# 7474-strobe-generator.net
KiCad netlist of a schematic drawn in EAGLE
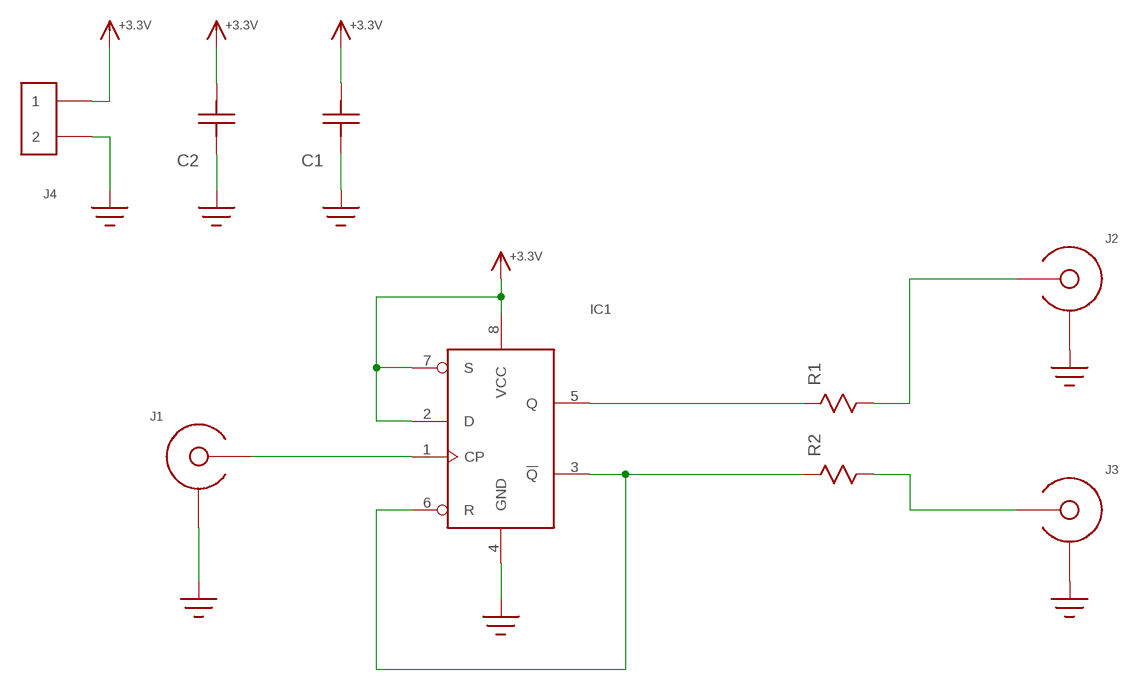
[diagram p0: schematic, sheet 1]

(export (version "E")
  (design (tool "Eeschema 10.0.6"))
  (components
    (comp (ref "C1")
      (value "C0603")
      (footprint "eagle-import:C0603")
      (libsource (lib "eagle-import") (part "C0603"))
    )
    (comp (ref "C2")
      (value "C1206")
      (footprint "eagle-import:1206")
      (libsource (lib "eagle-import") (part "C1206"))
    )
    (comp (ref "IC1")
      (value "74LVC2G74")
      (footprint "eagle-import:SSOP8")
      (libsource (lib "eagle-import") (part "74LVC2G74"))
    )
    (comp (ref "J1")
      (value "SMA-EDGE-LAUNCH4020_TAPER")
      (footprint "eagle-import:SMA_EDGE_LAUNCH_2L_4020_TAPER")
      (libsource (lib "eagle-import") (part "SMA-EDGE-LAUNCH4020_TAPER"))
    )
    (comp (ref "J2")
      (value "SMA-EDGE-LAUNCH4020_TAPER")
      (footprint "eagle-import:SMA_EDGE_LAUNCH_2L_4020_TAPER")
      (libsource (lib "eagle-import") (part "SMA-EDGE-LAUNCH4020_TAPER"))
    )
    (comp (ref "J3")
      (value "SMA-EDGE-LAUNCH4020_TAPER")
      (footprint "eagle-import:SMA_EDGE_LAUNCH_2L_4020_TAPER")
      (libsource (lib "eagle-import") (part "SMA-EDGE-LAUNCH4020_TAPER"))
    )
    (comp (ref "J4")
      (value "HEADER_2PIN")
      (footprint "eagle-import:HEADER_2PIN")
      (libsource (lib "eagle-import") (part "HEADER_2PIN"))
    )
    (comp (ref "R1")
      (value "R0603")
      (footprint "eagle-import:R0603")
      (libsource (lib "eagle-import") (part "R0603"))
    )
    (comp (ref "R2")
      (value "R0603")
      (footprint "eagle-import:R0603")
      (libsource (lib "eagle-import") (part "R0603"))
    )
  )
  (nets
    (net (code "1") (name "+3.3V") (class "Default")
      (node (ref "C1") (pin "P$1") (pinfunction "P$1_P$1") (pintype "bidirectional"))
      (node (ref "C2") (pin "P$1") (pinfunction "P$1_P$1") (pintype "bidirectional"))
      (node (ref "IC1") (pin "2") (pinfunction "D_2") (pintype "bidirectional"))
      (node (ref "IC1") (pin "7") (pinfunction "S_7") (pintype "bidirectional"))
      (node (ref "IC1") (pin "8") (pinfunction "VCC_8") (pintype "bidirectional"))
      (node (ref "J4") (pin "1") (pinfunction "1_1") (pintype "bidirectional"))
    )
    (net (code "2") (name "GND") (class "Default")
      (node (ref "C1") (pin "P$2") (pinfunction "P$2_P$2") (pintype "bidirectional"))
      (node (ref "C2") (pin "P$2") (pinfunction "P$2_P$2") (pintype "bidirectional"))
      (node (ref "IC1") (pin "4") (pinfunction "GND_4") (pintype "bidirectional"))
      (node (ref "J1") (pin "BOTTOM_GND") (pinfunction "SHIELD_BOTTOM_GND") (pintype "bidirectional"))
      (node (ref "J1") (pin "GND@1") (pinfunction "SHIELD_GND@1") (pintype "bidirectional"))
      (node (ref "J1") (pin "GND@14") (pinfunction "SHIELD_GND@14") (pintype "bidirectional"))
      (node (ref "J1") (pin "GND@15") (pinfunction "SHIELD_GND@15") (pintype "bidirectional"))
      (node (ref "J1") (pin "GND@16") (pinfunction "SHIELD_GND@16") (pintype "bidirectional"))
      (node (ref "J1") (pin "GND@17") (pinfunction "SHIELD_GND@17") (pintype "bidirectional"))
      (node (ref "J1") (pin "GND@2") (pinfunction "SHIELD_GND@2") (pintype "bidirectional"))
      (node (ref "J1") (pin "GND@3") (pinfunction "SHIELD_GND@3") (pintype "bidirectional"))
      (node (ref "J1") (pin "GND@4") (pinfunction "SHIELD_GND@4") (pintype "bidirectional"))
      (node (ref "J1") (pin "GND@5") (pinfunction "SHIELD_GND@5") (pintype "bidirectional"))
      (node (ref "J1") (pin "GND@6") (pinfunction "SHIELD_GND@6") (pintype "bidirectional"))
      (node (ref "J1") (pin "GND@7") (pinfunction "SHIELD_GND@7") (pintype "bidirectional"))
      (node (ref "J1") (pin "GND@8") (pinfunction "SHIELD_GND@8") (pintype "bidirectional"))
      (node (ref "J1") (pin "GND_PAD1") (pinfunction "SHIELD_GND_PAD1") (pintype "bidirectional"))
      (node (ref "J1") (pin "GND_PAD2") (pinfunction "SHIELD_GND_PAD2") (pintype "bidirectional"))
      (node (ref "J1") (pin "P$1") (pinfunction "SHIELD_P$1") (pintype "bidirectional"))
      (node (ref "J1") (pin "P$2") (pinfunction "SHIELD_P$2") (pintype "bidirectional"))
      (node (ref "J2") (pin "BOTTOM_GND") (pinfunction "SHIELD_BOTTOM_GND") (pintype "bidirectional"))
      (node (ref "J2") (pin "GND@1") (pinfunction "SHIELD_GND@1") (pintype "bidirectional"))
      (node (ref "J2") (pin "GND@14") (pinfunction "SHIELD_GND@14") (pintype "bidirectional"))
      (node (ref "J2") (pin "GND@15") (pinfunction "SHIELD_GND@15") (pintype "bidirectional"))
      (node (ref "J2") (pin "GND@16") (pinfunction "SHIELD_GND@16") (pintype "bidirectional"))
      (node (ref "J2") (pin "GND@17") (pinfunction "SHIELD_GND@17") (pintype "bidirectional"))
      (node (ref "J2") (pin "GND@2") (pinfunction "SHIELD_GND@2") (pintype "bidirectional"))
      (node (ref "J2") (pin "GND@3") (pinfunction "SHIELD_GND@3") (pintype "bidirectional"))
      (node (ref "J2") (pin "GND@4") (pinfunction "SHIELD_GND@4") (pintype "bidirectional"))
      (node (ref "J2") (pin "GND@5") (pinfunction "SHIELD_GND@5") (pintype "bidirectional"))
      (node (ref "J2") (pin "GND@6") (pinfunction "SHIELD_GND@6") (pintype "bidirectional"))
      (node (ref "J2") (pin "GND@7") (pinfunction "SHIELD_GND@7") (pintype "bidirectional"))
      (node (ref "J2") (pin "GND@8") (pinfunction "SHIELD_GND@8") (pintype "bidirectional"))
      (node (ref "J2") (pin "GND_PAD1") (pinfunction "SHIELD_GND_PAD1") (pintype "bidirectional"))
      (node (ref "J2") (pin "GND_PAD2") (pinfunction "SHIELD_GND_PAD2") (pintype "bidirectional"))
      (node (ref "J2") (pin "P$1") (pinfunction "SHIELD_P$1") (pintype "bidirectional"))
      (node (ref "J2") (pin "P$2") (pinfunction "SHIELD_P$2") (pintype "bidirectional"))
      (node (ref "J3") (pin "BOTTOM_GND") (pinfunction "SHIELD_BOTTOM_GND") (pintype "bidirectional"))
      (node (ref "J3") (pin "GND@1") (pinfunction "SHIELD_GND@1") (pintype "bidirectional"))
      (node (ref "J3") (pin "GND@14") (pinfunction "SHIELD_GND@14") (pintype "bidirectional"))
      (node (ref "J3") (pin "GND@15") (pinfunction "SHIELD_GND@15") (pintype "bidirectional"))
      (node (ref "J3") (pin "GND@16") (pinfunction "SHIELD_GND@16") (pintype "bidirectional"))
      (node (ref "J3") (pin "GND@17") (pinfunction "SHIELD_GND@17") (pintype "bidirectional"))
      (node (ref "J3") (pin "GND@2") (pinfunction "SHIELD_GND@2") (pintype "bidirectional"))
      (node (ref "J3") (pin "GND@3") (pinfunction "SHIELD_GND@3") (pintype "bidirectional"))
      (node (ref "J3") (pin "GND@4") (pinfunction "SHIELD_GND@4") (pintype "bidirectional"))
      (node (ref "J3") (pin "GND@5") (pinfunction "SHIELD_GND@5") (pintype "bidirectional"))
      (node (ref "J3") (pin "GND@6") (pinfunction "SHIELD_GND@6") (pintype "bidirectional"))
      (node (ref "J3") (pin "GND@7") (pinfunction "SHIELD_GND@7") (pintype "bidirectional"))
      (node (ref "J3") (pin "GND@8") (pinfunction "SHIELD_GND@8") (pintype "bidirectional"))
      (node (ref "J3") (pin "GND_PAD1") (pinfunction "SHIELD_GND_PAD1") (pintype "bidirectional"))
      (node (ref "J3") (pin "GND_PAD2") (pinfunction "SHIELD_GND_PAD2") (pintype "bidirectional"))
      (node (ref "J3") (pin "P$1") (pinfunction "SHIELD_P$1") (pintype "bidirectional"))
      (node (ref "J3") (pin "P$2") (pinfunction "SHIELD_P$2") (pintype "bidirectional"))
      (node (ref "J4") (pin "2") (pinfunction "2_2") (pintype "bidirectional"))
    )
    (net (code "3") (name "Net-(IC1-CP)") (class "Default")
      (node (ref "IC1") (pin "1") (pinfunction "CP_1") (pintype "bidirectional"))
      (node (ref "J1") (pin "CENTER@1") (pinfunction "CENTER_CENTER@1") (pintype "bidirectional"))
    )
    (net (code "4") (name "Net-(IC1-Q)") (class "Default")
      (node (ref "IC1") (pin "5") (pinfunction "Q_5") (pintype "bidirectional"))
      (node (ref "R1") (pin "P$1") (pinfunction "P$3_P$1") (pintype "bidirectional"))
    )
    (net (code "5") (name "Net-(IC1-R)") (class "Default")
      (node (ref "IC1") (pin "3") (pinfunction "~{Q}_3") (pintype "bidirectional"))
      (node (ref "IC1") (pin "6") (pinfunction "R_6") (pintype "bidirectional"))
      (node (ref "R2") (pin "P$1") (pinfunction "P$3_P$1") (pintype "bidirectional"))
    )
    (net (code "6") (name "Net-(J2-CENTER)") (class "Default")
      (node (ref "J2") (pin "CENTER@1") (pinfunction "CENTER_CENTER@1") (pintype "bidirectional"))
      (node (ref "R1") (pin "P$2") (pinfunction "P$4_P$2") (pintype "bidirectional"))
    )
    (net (code "7") (name "Net-(J3-CENTER)") (class "Default")
      (node (ref "J3") (pin "CENTER@1") (pinfunction "CENTER_CENTER@1") (pintype "bidirectional"))
      (node (ref "R2") (pin "P$2") (pinfunction "P$4_P$2") (pintype "bidirectional"))
    )
  )
)
